# yard-ice-cpu.net
KiCad netlist of a schematic drawn in Altium Designer
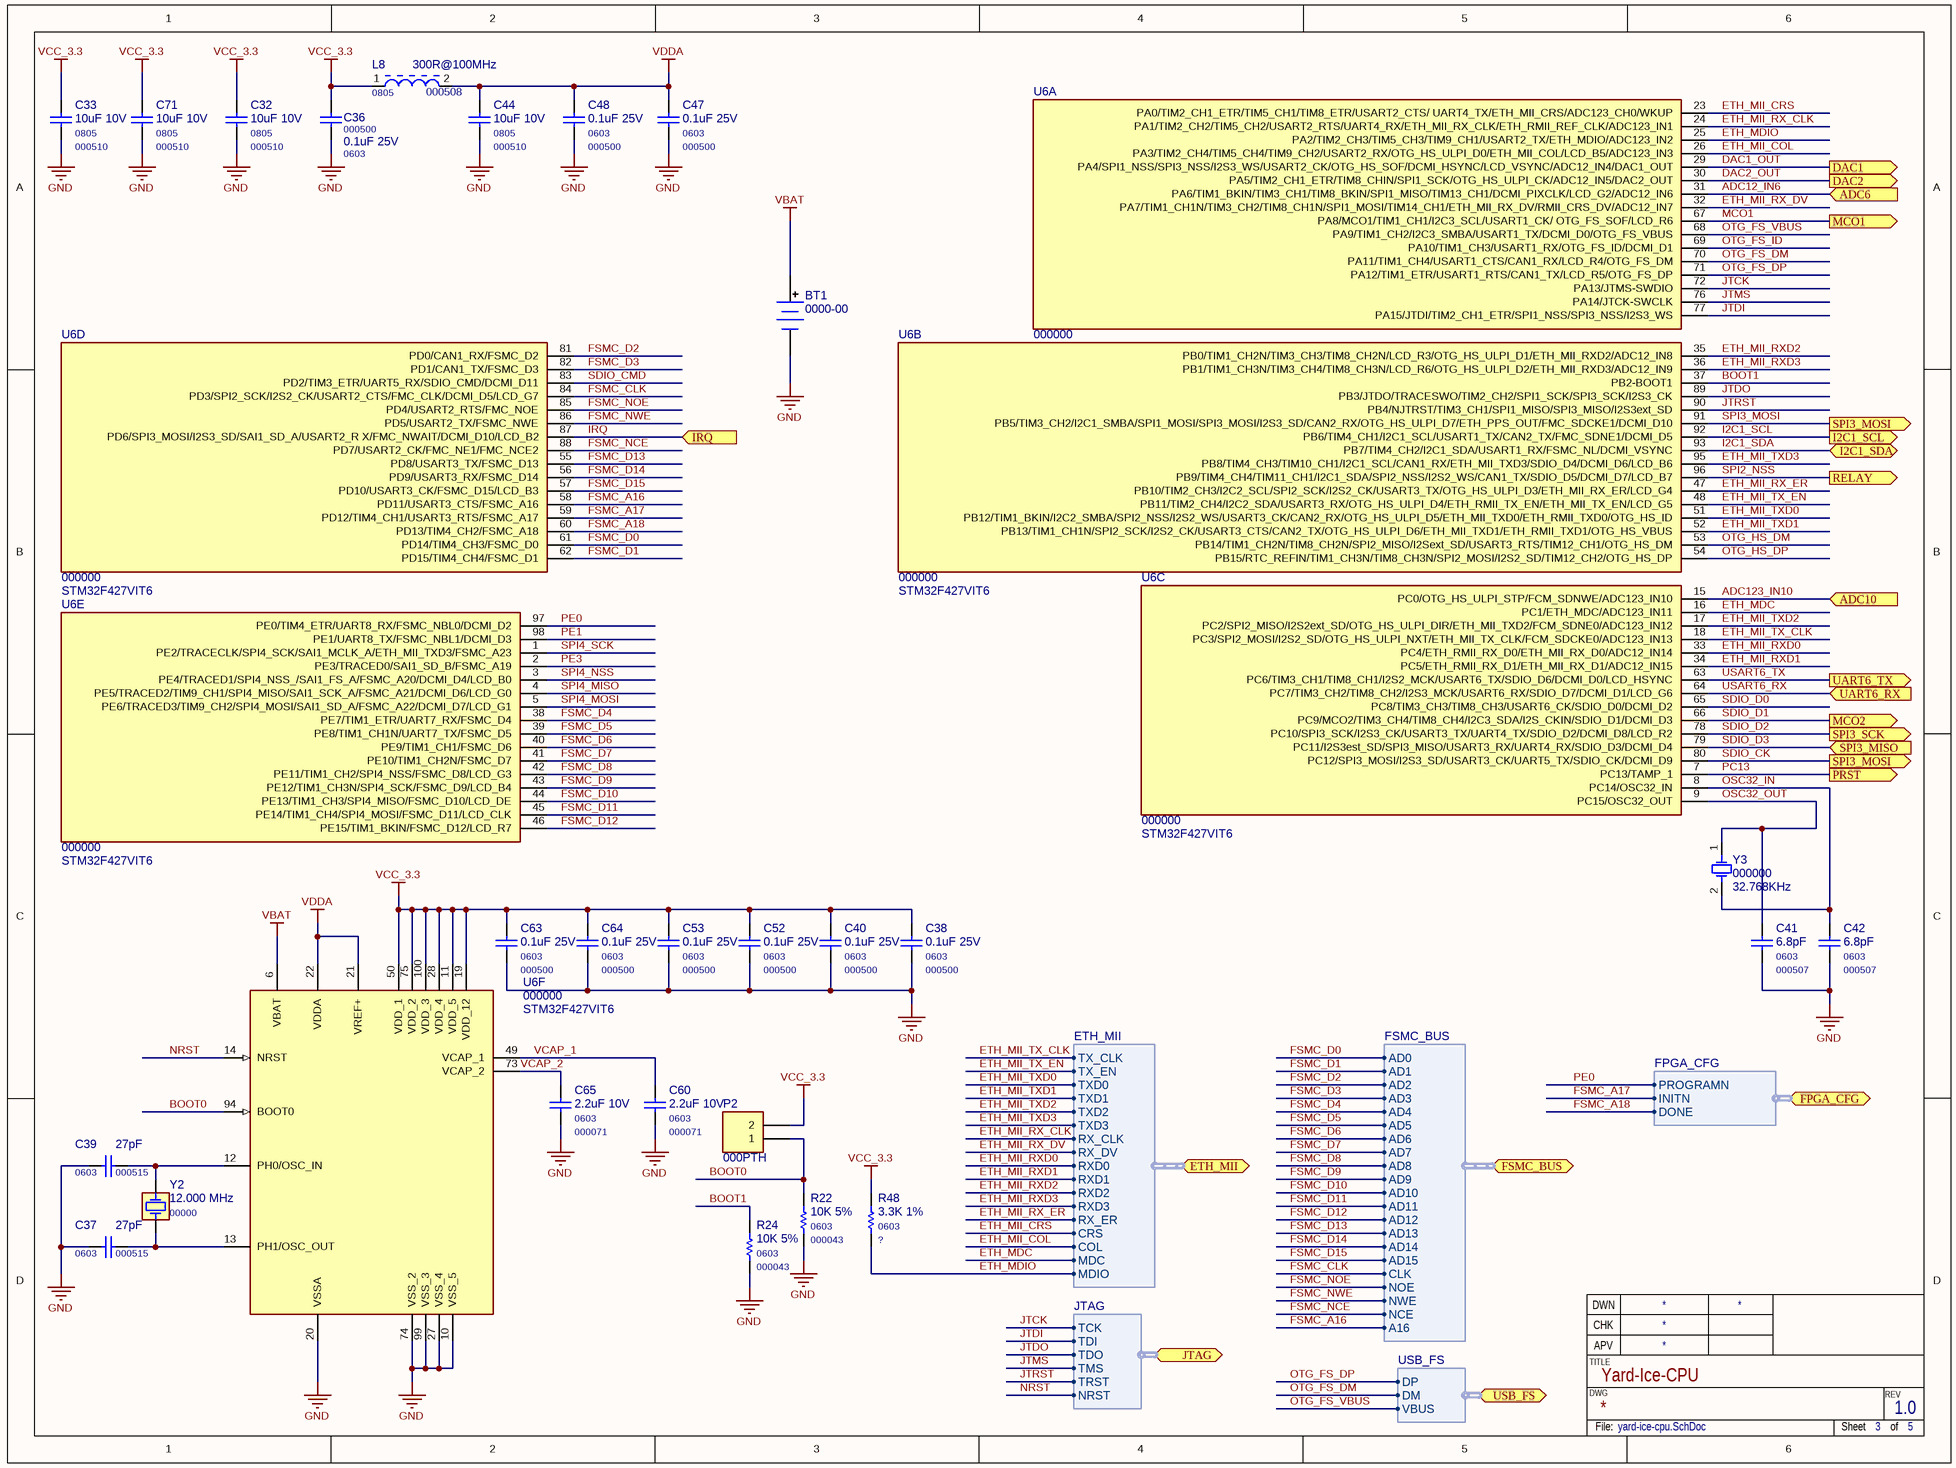
[diagram p0: yard-ice-cpu.SchDoc]

(export (version "E")
  (design (tool "Eeschema 10.0.6"))
  (components
    (comp (ref "BT1")
      (value "0000-00")
      (footprint "CR-1632/VCN")
      (description "PTH 16mm SMD Battery Vertical")
      (fields (field (name "MF") "Panasonic"))
      (libsource (lib "discrete-pth") (part "CR-1632/VCN"))
    )
    (comp (ref "C32")
      (value "TDK")
      (footprint "C0805M")
      (description "SMD Ceramic Chip Capacitor - 0805 - X7R")
      (fields (field (name "ALTIUM_VALUE") "10uF 10V") (field (name "PACKAGE") "0805"))
      (libsource (lib "discrete-sm") (part "C0805"))
    )
    (comp (ref "C33")
      (value "TDK")
      (footprint "C0805M")
      (description "SMD Ceramic Chip Capacitor - 0805 - X7R")
      (fields (field (name "ALTIUM_VALUE") "10uF 10V") (field (name "PACKAGE") "0805"))
      (libsource (lib "discrete-sm") (part "C0805"))
    )
    (comp (ref "C36")
      (value "000500")
      (footprint "C0603M")
      (description "SMD Ceramic Chip Capacitor - 0603 - X7R")
      (fields
        (field (name "ALTIUM_VALUE") "0.1uF 25V")
        (field (name "PACKAGE") "0603")
        (field (name "MF") "TDK")
      )
      (libsource (lib "discrete-sm") (part "C0603"))
    )
    (comp (ref "C37")
      (value "000515")
      (footprint "C0603M")
      (description "SMD Ceramic Chip Capacitor - 0603")
      (fields (field (name "ALTIUM_VALUE") "27pF") (field (name "PACKAGE") "0603"))
      (libsource (lib "discrete-sm") (part "C0603"))
    )
    (comp (ref "C38")
      (value "000500")
      (footprint "C0603M")
      (description "SMD Ceramic Chip Capacitor - 0603 - X7R")
      (fields
        (field (name "ALTIUM_VALUE") "0.1uF 25V")
        (field (name "PACKAGE") "0603")
        (field (name "MF") "TDK")
      )
      (libsource (lib "discrete-sm") (part "C0603"))
    )
    (comp (ref "C39")
      (value "000515")
      (footprint "C0603M")
      (description "SMD Ceramic Chip Capacitor - 0603")
      (fields (field (name "ALTIUM_VALUE") "27pF") (field (name "PACKAGE") "0603"))
      (libsource (lib "discrete-sm") (part "C0603"))
    )
    (comp (ref "C40")
      (value "000500")
      (footprint "C0603M")
      (description "SMD Ceramic Chip Capacitor - 0603 - X7R")
      (fields
        (field (name "ALTIUM_VALUE") "0.1uF 25V")
        (field (name "PACKAGE") "0603")
        (field (name "MF") "TDK")
      )
      (libsource (lib "discrete-sm") (part "C0603"))
    )
    (comp (ref "C41")
      (value "000507")
      (footprint "C0603M")
      (description "SMD Ceramic Chip Capacitor - 0603")
      (fields (field (name "ALTIUM_VALUE") "6.8pF") (field (name "PACKAGE") "0603"))
      (libsource (lib "discrete-sm") (part "C0603"))
    )
    (comp (ref "C42")
      (value "000507")
      (footprint "C0603M")
      (description "SMD Ceramic Chip Capacitor - 0603")
      (fields (field (name "ALTIUM_VALUE") "6.8pF") (field (name "PACKAGE") "0603"))
      (libsource (lib "discrete-sm") (part "C0603"))
    )
    (comp (ref "C44")
      (value "000510")
      (footprint "C0805M")
      (description "SMD Ceramic Chip Capacitor - 0805 - X7R")
      (fields
        (field (name "ALTIUM_VALUE") "10uF 10V")
        (field (name "PACKAGE") "0805")
        (field (name "MF") "TDK")
      )
      (libsource (lib "discrete-sm") (part "C0805"))
    )
    (comp (ref "C47")
      (value "000500")
      (footprint "C0603M")
      (description "SMD Ceramic Chip Capacitor - 0603 - X7R")
      (fields
        (field (name "ALTIUM_VALUE") "0.1uF 25V")
        (field (name "PACKAGE") "0603")
        (field (name "MF") "TDK")
      )
      (libsource (lib "discrete-sm") (part "C0603"))
    )
    (comp (ref "C48")
      (value "000500")
      (footprint "C0603M")
      (description "SMD Ceramic Chip Capacitor - 0603 - X7R")
      (fields
        (field (name "ALTIUM_VALUE") "0.1uF 25V")
        (field (name "PACKAGE") "0603")
        (field (name "MF") "TDK")
      )
      (libsource (lib "discrete-sm") (part "C0603"))
    )
    (comp (ref "C52")
      (value "000500")
      (footprint "C0603M")
      (description "SMD Ceramic Chip Capacitor - 0603 - X7R")
      (fields
        (field (name "ALTIUM_VALUE") "0.1uF 25V")
        (field (name "PACKAGE") "0603")
        (field (name "MF") "TDK")
      )
      (libsource (lib "discrete-sm") (part "C0603"))
    )
    (comp (ref "C53")
      (value "000500")
      (footprint "C0603M")
      (description "SMD Ceramic Chip Capacitor - 0603 - X7R")
      (fields
        (field (name "ALTIUM_VALUE") "0.1uF 25V")
        (field (name "PACKAGE") "0603")
        (field (name "MF") "TDK")
      )
      (libsource (lib "discrete-sm") (part "C0603"))
    )
    (comp (ref "C60")
      (value "000071")
      (footprint "C0603M")
      (description "SMD Ceramic Chip Capacitor - 0603 - X7R")
      (fields
        (field (name "ALTIUM_VALUE") "2.2uF 10V")
        (field (name "PACKAGE") "0603")
        (field (name "MF") "Taiyo Yuden")
      )
      (libsource (lib "discrete-sm") (part "C0603"))
    )
    (comp (ref "C63")
      (value "000500")
      (footprint "C0603M")
      (description "SMD Ceramic Chip Capacitor - 0603 - X7R")
      (fields
        (field (name "ALTIUM_VALUE") "0.1uF 25V")
        (field (name "PACKAGE") "0603")
        (field (name "MF") "TDK")
      )
      (libsource (lib "discrete-sm") (part "C0603"))
    )
    (comp (ref "C64")
      (value "000500")
      (footprint "C0603M")
      (description "SMD Ceramic Chip Capacitor - 0603 - X7R")
      (fields
        (field (name "ALTIUM_VALUE") "0.1uF 25V")
        (field (name "PACKAGE") "0603")
        (field (name "MF") "TDK")
      )
      (libsource (lib "discrete-sm") (part "C0603"))
    )
    (comp (ref "C65")
      (value "000071")
      (footprint "C0603M")
      (description "SMD Ceramic Chip Capacitor - 0603 - X7R")
      (fields
        (field (name "ALTIUM_VALUE") "2.2uF 10V")
        (field (name "PACKAGE") "0603")
        (field (name "MF") "Taiyo Yuden")
      )
      (libsource (lib "discrete-sm") (part "C0603"))
    )
    (comp (ref "C71")
      (value "TDK")
      (footprint "C0805M")
      (description "SMD Ceramic Chip Capacitor - 0805 - X7R")
      (fields (field (name "ALTIUM_VALUE") "10uF 10V") (field (name "PACKAGE") "0805"))
      (libsource (lib "discrete-sm") (part "C0805"))
    )
    (comp (ref "L8")
      (value "000508")
      (footprint "L0805M")
      (description "SMD Ferrite Bead 0805")
      (fields
        (field (name "ALTIUM_VALUE") "300R@100MHz")
        (field (name "PACKAGE") "0805")
        (field (name "MF") "TDK")
      )
      (libsource (lib "discrete-sm") (part "L0805"))
    )
    (comp (ref "P2")
      (value "000PTH")
      (footprint "TSW-102-07-G-S")
      (description "Header, 2-Pin")
      (libsource (lib "samtec-board-to-board") (part "Header 2"))
    )
    (comp (ref "R22")
      (value "000043")
      (footprint "R0603M")
      (description "SMD Chip Resistor - 0603")
      (fields (field (name "ALTIUM_VALUE") "10K 5%") (field (name "PACKAGE") "0603"))
      (libsource (lib "discrete-sm") (part "R0603"))
    )
    (comp (ref "R24")
      (value "000043")
      (footprint "R0603M")
      (description "SMD Chip Resistor - 0603")
      (fields (field (name "ALTIUM_VALUE") "10K 5%") (field (name "PACKAGE") "0603"))
      (libsource (lib "discrete-sm") (part "R0603"))
    )
    (comp (ref "R48")
      (value "?")
      (footprint "R0603M")
      (description "SMD Chip Resistor - 0603")
      (fields (field (name "ALTIUM_VALUE") "3.3K 1%") (field (name "PACKAGE") "0603"))
      (libsource (lib "discrete-sm") (part "R0603"))
    )
    (comp (ref "U6")
      (value "000000")
      (footprint "LQFP100")
      (description "ARM Cortex-M4,  2MB Flash, 256+4KB RAM")
      (fields (field (name "ALTIUM_VALUE") "STM32F427VIT6"))
      (libsource (lib "st") (part "STM32F427VIT6"))
    )
    (comp (ref "Y2")
      (value "00000")
      (footprint "ABM3-H")
      (description "Miniature Ceramic SMD Crystal")
      (fields (field (name "MF") "Abracon") (field (name "ALTIUM_VALUE") "12.000 MHz"))
      (libsource (lib "abracon") (part "ABM3"))
    )
    (comp (ref "Y3")
      (value "000000")
      (footprint "CA-301-V")
      (description "Cylinder Crystal Unit")
      (fields (field (name "MF") "Epson") (field (name "ALTIUM_VALUE") "32.768KHz"))
      (libsource (lib "epson-xtal") (part "CA-301"))
    )
  )
  (nets
    (net (code "6") (name "/ADC12_IN6") (class "Default")
      (node (ref "U6") (pin "31") (pinfunction "PA6/TIM1_BKIN/TIM3_CH1/TIM8_BKIN/SPI1_MISO/TIM13_CH1/DCMI_PIXCLK/LCD_G2/ADC12_IN6_31") (pintype "tri_state"))
    )
    (net (code "7") (name "/ADC123_IN10") (class "Default")
      (node (ref "U6") (pin "15") (pinfunction "PC0/OTG_HS_ULPI_STP/FCM_SDNWE/ADC123_IN10_15") (pintype "tri_state"))
    )
    (net (code "8") (name "/BOOT0") (class "Default")
      (node (ref "P2") (pin "1") (pinfunction "1_1") (pintype "passive"))
      (node (ref "R22") (pin "2") (pinfunction "2_2") (pintype "passive"))
      (node (ref "U6") (pin "94") (pinfunction "BOOT0_94") (pintype "input"))
    )
    (net (code "9") (name "/BOOT1") (class "Default")
      (node (ref "R24") (pin "2") (pinfunction "2_2") (pintype "passive"))
      (node (ref "U6") (pin "37") (pinfunction "PB2-BOOT1_37") (pintype "tri_state"))
    )
    (net (code "10") (name "/DAC1_OUT") (class "Default")
      (node (ref "U6") (pin "29") (pinfunction "PA4/SPI1_NSS/SPI3_NSS/I2S3_WS/USART2_CK/OTG_HS_SOF/DCMI_HSYNC/LCD_VSYNC/ADC12_IN4/DAC1_OUT_29") (pintype "tri_state"))
    )
    (net (code "11") (name "/DAC2_OUT") (class "Default")
      (node (ref "U6") (pin "30") (pinfunction "PA5/TIM2_CH1_ETR/TIM8_CHIN/SPI1_SCK/OTG_HS_ULPI_CK/ADC12_IN5/DAC2_OUT_30") (pintype "tri_state"))
    )
    (net (code "12") (name "/ETH_MDC") (class "Default")
      (node (ref "U6") (pin "16") (pinfunction "PC1/ETH_MDC/ADC123_IN11_16") (pintype "tri_state"))
    )
    (net (code "13") (name "/ETH_MDIO") (class "Default")
      (node (ref "R48") (pin "1") (pinfunction "1_1") (pintype "passive"))
      (node (ref "U6") (pin "25") (pinfunction "PA2/TIM2_CH3/TIM5_CH3/TIM9_CH1/USART2_TX/ETH_MDIO/ADC123_IN2_25") (pintype "tri_state"))
    )
    (net (code "14") (name "/ETH_MII_COL") (class "Default")
      (node (ref "U6") (pin "26") (pinfunction "PA3/TIM2_CH4/TIM5_CH4/TIM9_CH2/USART2_RX/OTG_HS_ULPI_D0/ETH_MII_COL/LCD_B5/ADC123_IN3_26") (pintype "tri_state"))
    )
    (net (code "15") (name "/ETH_MII_CRS") (class "Default")
      (node (ref "U6") (pin "23") (pinfunction "PA0/TIM2_CH1_ETR/TIM5_CH1/TIM8_ETR/USART2_CTS/_UART4_TX/ETH_MII_CRS/ADC123_CH0/WKUP_23") (pintype "tri_state"))
    )
    (net (code "16") (name "/ETH_MII_RXD0") (class "Default")
      (node (ref "U6") (pin "33") (pinfunction "PC4/ETH_RMII_RX_D0/ETH_MII_RX_D0/ADC12_IN14_33") (pintype "tri_state"))
    )
    (net (code "17") (name "/ETH_MII_RXD1") (class "Default")
      (node (ref "U6") (pin "34") (pinfunction "PC5/ETH_RMII_RX_D1/ETH_MII_RX_D1/ADC12_IN15_34") (pintype "tri_state"))
    )
    (net (code "18") (name "/ETH_MII_RXD2") (class "Default")
      (node (ref "U6") (pin "35") (pinfunction "PB0/TIM1_CH2N/TIM3_CH3/TIM8_CH2N/LCD_R3/OTG_HS_ULPI_D1/ETH_MII_RXD2/ADC12_IN8_35") (pintype "tri_state"))
    )
    (net (code "19") (name "/ETH_MII_RXD3") (class "Default")
      (node (ref "U6") (pin "36") (pinfunction "PB1/TIM1_CH3N/TIM3_CH4/TIM8_CH3N/LCD_R6/OTG_HS_ULPI_D2/ETH_MII_RXD3/ADC12_IN9_36") (pintype "tri_state"))
    )
    (net (code "20") (name "/ETH_MII_RX_CLK") (class "Default")
      (node (ref "U6") (pin "24") (pinfunction "PA1/TIM2_CH2/TIM5_CH2/USART2_RTS/UART4_RX/ETH_MII_RX_CLK/ETH_RMII_REF_CLK/ADC123_IN1_24") (pintype "tri_state"))
    )
    (net (code "21") (name "/ETH_MII_RX_DV") (class "Default")
      (node (ref "U6") (pin "32") (pinfunction "PA7/TIM1_CH1N/TIM3_CH2/TIM8_CH1N/SPI1_MOSI/TIM14_CH1/ETH_MII_RX_DV/RMII_CRS_DV/ADC12_IN7_32") (pintype "tri_state"))
    )
    (net (code "22") (name "/ETH_MII_RX_ER") (class "Default")
      (node (ref "U6") (pin "47") (pinfunction "PB10/TIM2_CH3/I2C2_SCL/SPI2_SCK/I2S2_CK/USART3_TX/OTG_HS_ULPI_D3/ETH_MII_RX_ER/LCD_G4_47") (pintype "tri_state"))
    )
    (net (code "23") (name "/ETH_MII_TXD0") (class "Default")
      (node (ref "U6") (pin "51") (pinfunction "PB12/TIM1_BKIN/I2C2_SMBA/SPI2_NSS/I2S2_WS/USART3_CK/CAN2_RX/OTG_HS_ULPI_D5/ETH_MII_TXD0/ETH_RMII_TXD0/OTG_HS_ID_51") (pintype "tri_state"))
    )
    (net (code "24") (name "/ETH_MII_TXD1") (class "Default")
      (node (ref "U6") (pin "52") (pinfunction "PB13/TIM1_CH1N/SPI2_SCK/I2S2_CK/USART3_CTS/CAN2_TX/OTG_HS_ULPI_D6/ETH_MII_TXD1/ETH_RMII_TXD1/OTG_HS_VBUS_52") (pintype "tri_state"))
    )
    (net (code "25") (name "/ETH_MII_TXD2") (class "Default")
      (node (ref "U6") (pin "17") (pinfunction "PC2/SPI2_MISO/I2S2ext_SD/OTG_HS_ULPI_DIR/ETH_MII_TXD2/FCM_SDNE0/ADC123_IN12_17") (pintype "tri_state"))
    )
    (net (code "26") (name "/ETH_MII_TXD3") (class "Default")
      (node (ref "U6") (pin "95") (pinfunction "PB8/TIM4_CH3/TIM10_CH1/I2C1_SCL/CAN1_RX/ETH_MII_TXD3/SDIO_D4/DCMI_D6/LCD_B6_95") (pintype "tri_state"))
    )
    (net (code "27") (name "/ETH_MII_TX_CLK") (class "Default")
      (node (ref "U6") (pin "18") (pinfunction "PC3/SPI2_MOSI/I2S2_SD/OTG_HS_ULPI_NXT/ETH_MII_TX_CLK/FCM_SDCKE0/ADC123_IN13_18") (pintype "tri_state"))
    )
    (net (code "28") (name "/ETH_MII_TX_EN") (class "Default")
      (node (ref "U6") (pin "48") (pinfunction "PB11/TIM2_CH4/I2C2_SDA/USART3_RX/OTG_HS_ULPI_D4/ETH_RMII_TX_EN/ETH_MII_TX_EN/LCD_G5_48") (pintype "tri_state"))
    )
    (net (code "29") (name "/FSMC_A16") (class "Default")
      (node (ref "U6") (pin "58") (pinfunction "PD11/USART3_CTS/FSMC_A16_58") (pintype "tri_state"))
    )
    (net (code "30") (name "/FSMC_A17") (class "Default")
      (node (ref "U6") (pin "59") (pinfunction "PD12/TIM4_CH1/USART3_RTS/FSMC_A17_59") (pintype "tri_state"))
    )
    (net (code "31") (name "/FSMC_A18") (class "Default")
      (node (ref "U6") (pin "60") (pinfunction "PD13/TIM4_CH2/FSMC_A18_60") (pintype "tri_state"))
    )
    (net (code "32") (name "/FSMC_CLK") (class "Default")
      (node (ref "U6") (pin "84") (pinfunction "PD3/SPI2_SCK/I2S2_CK/USART2_CTS/FMC_CLK/DCMI_D5/LCD_G7_84") (pintype "tri_state"))
    )
    (net (code "33") (name "/FSMC_D0") (class "Default")
      (node (ref "U6") (pin "61") (pinfunction "PD14/TIM4_CH3/FSMC_D0_61") (pintype "tri_state"))
    )
    (net (code "34") (name "/FSMC_D1") (class "Default")
      (node (ref "U6") (pin "62") (pinfunction "PD15/TIM4_CH4/FSMC_D1_62") (pintype "tri_state"))
    )
    (net (code "35") (name "/FSMC_D2") (class "Default")
      (node (ref "U6") (pin "81") (pinfunction "PD0/CAN1_RX/FSMC_D2_81") (pintype "tri_state"))
    )
    (net (code "36") (name "/FSMC_D3") (class "Default")
      (node (ref "U6") (pin "82") (pinfunction "PD1/CAN1_TX/FSMC_D3_82") (pintype "tri_state"))
    )
    (net (code "37") (name "/FSMC_D4") (class "Default")
      (node (ref "U6") (pin "38") (pinfunction "PE7/TIM1_ETR/UART7_RX/FSMC_D4_38") (pintype "tri_state"))
    )
    (net (code "38") (name "/FSMC_D5") (class "Default")
      (node (ref "U6") (pin "39") (pinfunction "PE8/TIM1_CH1N/UART7_TX/FSMC_D5_39") (pintype "tri_state"))
    )
    (net (code "39") (name "/FSMC_D6") (class "Default")
      (node (ref "U6") (pin "40") (pinfunction "PE9/TIM1_CH1/FSMC_D6_40") (pintype "tri_state"))
    )
    (net (code "40") (name "/FSMC_D7") (class "Default")
      (node (ref "U6") (pin "41") (pinfunction "PE10/TIM1_CH2N/FSMC_D7_41") (pintype "tri_state"))
    )
    (net (code "41") (name "/FSMC_D8") (class "Default")
      (node (ref "U6") (pin "42") (pinfunction "PE11/TIM1_CH2/SPI4_NSS/FSMC_D8/LCD_G3_42") (pintype "tri_state"))
    )
    (net (code "42") (name "/FSMC_D9") (class "Default")
      (node (ref "U6") (pin "43") (pinfunction "PE12/TIM1_CH3N/SPI4_SCK/FSMC_D9/LCD_B4_43") (pintype "tri_state"))
    )
    (net (code "43") (name "/FSMC_D10") (class "Default")
      (node (ref "U6") (pin "44") (pinfunction "PE13/TIM1_CH3/SPI4_MISO/FSMC_D10/LCD_DE_44") (pintype "tri_state"))
    )
    (net (code "44") (name "/FSMC_D11") (class "Default")
      (node (ref "U6") (pin "45") (pinfunction "PE14/TIM1_CH4/SPI4_MOSI/FSMC_D11/LCD_CLK_45") (pintype "tri_state"))
    )
    (net (code "45") (name "/FSMC_D12") (class "Default")
      (node (ref "U6") (pin "46") (pinfunction "PE15/TIM1_BKIN/FSMC_D12/LCD_R7_46") (pintype "tri_state"))
    )
    (net (code "46") (name "/FSMC_D13") (class "Default")
      (node (ref "U6") (pin "55") (pinfunction "PD8/USART3_TX/FSMC_D13_55") (pintype "tri_state"))
    )
    (net (code "47") (name "/FSMC_D14") (class "Default")
      (node (ref "U6") (pin "56") (pinfunction "PD9/USART3_RX/FSMC_D14_56") (pintype "tri_state"))
    )
    (net (code "48") (name "/FSMC_D15") (class "Default")
      (node (ref "U6") (pin "57") (pinfunction "PD10/USART3_CK/FSMC_D15/LCD_B3_57") (pintype "tri_state"))
    )
    (net (code "49") (name "/FSMC_NCE") (class "Default")
      (node (ref "U6") (pin "88") (pinfunction "PD7/USART2_CK/FMC_NE1/FMC_NCE2_88") (pintype "tri_state"))
    )
    (net (code "50") (name "/FSMC_NOE") (class "Default")
      (node (ref "U6") (pin "85") (pinfunction "PD4/USART2_RTS/FMC_NOE_85") (pintype "tri_state"))
    )
    (net (code "51") (name "/FSMC_NWE") (class "Default")
      (node (ref "U6") (pin "86") (pinfunction "PD5/USART2_TX/FSMC_NWE_86") (pintype "tri_state"))
    )
    (net (code "52") (name "/I2C1_SCL") (class "Default")
      (node (ref "U6") (pin "92") (pinfunction "PB6/TIM4_CH1/I2C1_SCL/USART1_TX/CAN2_TX/FMC_SDNE1/DCMI_D5_92") (pintype "tri_state"))
    )
    (net (code "53") (name "/I2C1_SDA") (class "Default")
      (node (ref "U6") (pin "93") (pinfunction "PB7/TIM4_CH2/I2C1_SDA/USART1_RX/FSMC_NL/DCMI_VSYNC_93") (pintype "tri_state"))
    )
    (net (code "54") (name "/IRQ") (class "Default")
      (node (ref "U6") (pin "87") (pinfunction "PD6/SPI3_MOSI/I2S3_SD/SAI1_SD_A/USART2_R_X/FMC_NWAIT/DCMI_D10/LCD_B2_87") (pintype "tri_state"))
    )
    (net (code "55") (name "/JTCK") (class "Default")
      (node (ref "U6") (pin "72") (pinfunction "PA13/JTMS-SWDIO_72") (pintype "tri_state"))
    )
    (net (code "56") (name "/JTDI") (class "Default")
      (node (ref "U6") (pin "77") (pinfunction "PA15/JTDI/TIM2_CH1_ETR/SPI1_NSS/SPI3_NSS/I2S3_WS_77") (pintype "tri_state"))
    )
    (net (code "57") (name "/JTDO") (class "Default")
      (node (ref "U6") (pin "89") (pinfunction "PB3/JTDO/TRACESWO/TIM2_CH2/SPI1_SCK/SPI3_SCK/I2S3_CK_89") (pintype "tri_state"))
    )
    (net (code "58") (name "/JTMS") (class "Default")
      (node (ref "U6") (pin "76") (pinfunction "PA14/JTCK-SWCLK_76") (pintype "tri_state"))
    )
    (net (code "59") (name "/JTRST") (class "Default")
      (node (ref "U6") (pin "90") (pinfunction "PB4/NJTRST/TIM3_CH1/SPI1_MISO/SPI3_MISO/I2S3ext_SD_90") (pintype "tri_state"))
    )
    (net (code "60") (name "/MCO1") (class "Default")
      (node (ref "U6") (pin "67") (pinfunction "PA8/MCO1/TIM1_CH1/I2C3_SCL/USART1_CK/_OTG_FS_SOF/LCD_R6_67") (pintype "tri_state"))
    )
    (net (code "61") (name "/NRST") (class "Default")
      (node (ref "U6") (pin "14") (pinfunction "NRST_14") (pintype "input"))
    )
    (net (code "62") (name "/OSC32_IN") (class "Default")
      (node (ref "C42") (pin "2") (pinfunction "2_2") (pintype "passive"))
      (node (ref "U6") (pin "8") (pinfunction "PC14/OSC32_IN_8") (pintype "tri_state"))
      (node (ref "Y3") (pin "2") (pinfunction "2_2") (pintype "passive"))
    )
    (net (code "63") (name "/OSC32_OUT") (class "Default")
      (node (ref "C41") (pin "2") (pinfunction "2_2") (pintype "passive"))
      (node (ref "U6") (pin "9") (pinfunction "PC15/OSC32_OUT_9") (pintype "tri_state"))
      (node (ref "Y3") (pin "1") (pinfunction "1_1") (pintype "passive"))
    )
    (net (code "64") (name "/OTG_FS_DM") (class "Default")
      (node (ref "U6") (pin "70") (pinfunction "PA11/TIM1_CH4/USART1_CTS/CAN1_RX/LCD_R4/OTG_FS_DM_70") (pintype "tri_state"))
    )
    (net (code "65") (name "/OTG_FS_DP") (class "Default")
      (node (ref "U6") (pin "71") (pinfunction "PA12/TIM1_ETR/USART1_RTS/CAN1_TX/LCD_R5/OTG_FS_DP_71") (pintype "tri_state"))
    )
    (net (code "66") (name "/OTG_FS_ID") (class "Default")
      (node (ref "U6") (pin "69") (pinfunction "PA10/TIM1_CH3/USART1_RX/OTG_FS_ID/DCMI_D1_69") (pintype "tri_state"))
    )
    (net (code "67") (name "/OTG_FS_VBUS") (class "Default")
      (node (ref "U6") (pin "68") (pinfunction "PA9/TIM1_CH2/I2C3_SMBA/USART1_TX/DCMI_D0/OTG_FS_VBUS_68") (pintype "tri_state"))
    )
    (net (code "68") (name "/OTG_HS_DM") (class "Default")
      (node (ref "U6") (pin "53") (pinfunction "PB14/TIM1_CH2N/TIM8_CH2N/SPI2_MISO/I2Sext_SD/USART3_RTS/TIM12_CH1/OTG_HS_DM_53") (pintype "tri_state"))
    )
    (net (code "69") (name "/OTG_HS_DP") (class "Default")
      (node (ref "U6") (pin "54") (pinfunction "PB15/RTC_REFIN/TIM1_CH3N/TIM8_CH3N/SPI2_MOSI/I2S2_SD/TIM12_CH2/OTG_HS_DP_54") (pintype "tri_state"))
    )
    (net (code "70") (name "/PC13") (class "Default")
      (node (ref "U6") (pin "7") (pinfunction "PC13/TAMP_1_7") (pintype "tri_state"))
    )
    (net (code "71") (name "/PE0") (class "Default")
      (node (ref "U6") (pin "97") (pinfunction "PE0/TIM4_ETR/UART8_RX/FSMC_NBL0/DCMI_D2_97") (pintype "tri_state"))
    )
    (net (code "72") (name "/PE1") (class "Default")
      (node (ref "U6") (pin "98") (pinfunction "PE1/UART8_TX/FSMC_NBL1/DCMI_D3_98") (pintype "tri_state"))
    )
    (net (code "73") (name "/PE3") (class "Default")
      (node (ref "U6") (pin "2") (pinfunction "PE3/TRACED0/SAI1_SD_B/FSMC_A19_2") (pintype "tri_state"))
    )
    (net (code "74") (name "/SDIO_CK") (class "Default")
      (node (ref "U6") (pin "80") (pinfunction "PC12/SPI3_MOSI/I2S3_SD/USART3_CK/UART5_TX/SDIO_CK/DCMI_D9_80") (pintype "tri_state"))
      (node (ref "U6") (pin "91") (pinfunction "PB5/TIM3_CH2/I2C1_SMBA/SPI1_MOSI/SPI3_MOSI/I2S3_SD/CAN2_RX/OTG_HS_ULPI_D7/ETH_PPS_OUT/FMC_SDCKE1/DCMI_D10_91") (pintype "tri_state"))
    )
    (net (code "75") (name "/SDIO_CMD") (class "Default")
      (node (ref "U6") (pin "83") (pinfunction "PD2/TIM3_ETR/UART5_RX/SDIO_CMD/DCMI_D11_83") (pintype "tri_state"))
    )
    (net (code "76") (name "/SDIO_D0") (class "Default")
      (node (ref "U6") (pin "65") (pinfunction "PC8/TIM3_CH3/TIM8_CH3/USART6_CK/SDIO_D0/DCMI_D2_65") (pintype "tri_state"))
    )
    (net (code "77") (name "/SDIO_D1") (class "Default")
      (node (ref "U6") (pin "66") (pinfunction "PC9/MCO2/TIM3_CH4/TIM8_CH4/I2C3_SDA/I2S_CKIN/SDIO_D1/DCMI_D3_66") (pintype "tri_state"))
    )
    (net (code "78") (name "/SDIO_D2") (class "Default")
      (node (ref "U6") (pin "78") (pinfunction "PC10/SPI3_SCK/I2S3_CK/USART3_TX/UART4_TX/SDIO_D2/DCMI_D8/LCD_R2_78") (pintype "tri_state"))
    )
    (net (code "79") (name "/SDIO_D3") (class "Default")
      (node (ref "U6") (pin "79") (pinfunction "PC11/I2S3est_SD/SPI3_MISO/USART3_RX/UART4_RX/SDIO_D3/DCMI_D4_79") (pintype "tri_state"))
    )
    (net (code "80") (name "/SPI2_NSS") (class "Default")
      (node (ref "U6") (pin "96") (pinfunction "PB9/TIM4_CH4/TIM11_CH1/I2C1_SDA/SPI2_NSS/I2S2_WS/CAN1_TX/SDIO_D5/DCMI_D7/LCD_B7_96") (pintype "tri_state"))
    )
    (net (code "81") (name "/SPI4_MISO") (class "Default")
      (node (ref "U6") (pin "4") (pinfunction "PE5/TRACED2/TIM9_CH1/SPI4_MISO/SAI1_SCK_A/FSMC_A21/DCMI_D6/LCD_G0_4") (pintype "tri_state"))
    )
    (net (code "82") (name "/SPI4_MOSI") (class "Default")
      (node (ref "U6") (pin "5") (pinfunction "PE6/TRACED3/TIM9_CH2/SPI4_MOSI/SAI1_SD_A/FSMC_A22/DCMI_D7/LCD_G1_5") (pintype "tri_state"))
    )
    (net (code "83") (name "/SPI4_NSS") (class "Default")
      (node (ref "U6") (pin "3") (pinfunction "PE4/TRACED1/SPI4_NSS_/SAI1_FS_A/FSMC_A20/DCMI_D4/LCD_B0_3") (pintype "tri_state"))
    )
    (net (code "84") (name "/SPI4_SCK") (class "Default")
      (node (ref "U6") (pin "1") (pinfunction "PE2/TRACECLK/SPI4_SCK/SAI1_MCLK_A/ETH_MII_TXD3/FSMC_A23_1") (pintype "tri_state"))
    )
    (net (code "85") (name "/USART6_RX") (class "Default")
      (node (ref "U6") (pin "64") (pinfunction "PC7/TIM3_CH2/TIM8_CH2/I2S3_MCK/USART6_RX/SDIO_D7/DCMI_D1/LCD_G6_64") (pintype "tri_state"))
    )
    (net (code "86") (name "/USART6_TX") (class "Default")
      (node (ref "U6") (pin "63") (pinfunction "PC6/TIM3_CH1/TIM8_CH1/I2S2_MCK/USART6_TX/SDIO_D6/DCMI_D0/LCD_HSYNC_63") (pintype "tri_state"))
    )
    (net (code "87") (name "/VCAP_1") (class "Default")
      (node (ref "C60") (pin "1") (pinfunction "1_1") (pintype "passive"))
      (node (ref "U6") (pin "49") (pinfunction "VCAP_1_49") (pintype "power_in"))
    )
    (net (code "88") (name "/VCAP_2") (class "Default")
      (node (ref "C65") (pin "1") (pinfunction "1_1") (pintype "passive"))
      (node (ref "U6") (pin "73") (pinfunction "VCAP_2_73") (pintype "power_in"))
    )
    (net (code "94") (name "GND") (class "Default")
      (node (ref "BT1") (pin "2") (pinfunction "-_2") (pintype "passive"))
      (node (ref "C32") (pin "2") (pinfunction "2_2") (pintype "passive"))
      (node (ref "C33") (pin "2") (pinfunction "2_2") (pintype "passive"))
      (node (ref "C36") (pin "2") (pinfunction "2_2") (pintype "passive"))
      (node (ref "C37") (pin "1") (pinfunction "1_1") (pintype "passive"))
      (node (ref "C38") (pin "2") (pinfunction "2_2") (pintype "passive"))
      (node (ref "C39") (pin "1") (pinfunction "1_1") (pintype "passive"))
      (node (ref "C40") (pin "2") (pinfunction "2_2") (pintype "passive"))
      (node (ref "C41") (pin "1") (pinfunction "1_1") (pintype "passive"))
      (node (ref "C42") (pin "1") (pinfunction "1_1") (pintype "passive"))
      (node (ref "C44") (pin "2") (pinfunction "2_2") (pintype "passive"))
      (node (ref "C47") (pin "2") (pinfunction "2_2") (pintype "passive"))
      (node (ref "C48") (pin "2") (pinfunction "2_2") (pintype "passive"))
      (node (ref "C52") (pin "2") (pinfunction "2_2") (pintype "passive"))
      (node (ref "C53") (pin "2") (pinfunction "2_2") (pintype "passive"))
      (node (ref "C60") (pin "2") (pinfunction "2_2") (pintype "passive"))
      (node (ref "C63") (pin "2") (pinfunction "2_2") (pintype "passive"))
      (node (ref "C64") (pin "2") (pinfunction "2_2") (pintype "passive"))
      (node (ref "C65") (pin "2") (pinfunction "2_2") (pintype "passive"))
      (node (ref "C71") (pin "2") (pinfunction "2_2") (pintype "passive"))
      (node (ref "R22") (pin "1") (pinfunction "1_1") (pintype "passive"))
      (node (ref "R24") (pin "1") (pinfunction "1_1") (pintype "passive"))
      (node (ref "U6") (pin "10") (pinfunction "VSS_5_10") (pintype "power_in"))
      (node (ref "U6") (pin "20") (pinfunction "VSSA_20") (pintype "power_in"))
      (node (ref "U6") (pin "27") (pinfunction "VSS_4_27") (pintype "power_in"))
      (node (ref "U6") (pin "74") (pinfunction "VSS_2_74") (pintype "power_in"))
      (node (ref "U6") (pin "99") (pinfunction "VSS_3_99") (pintype "passive"))
    )
    (net (code "95") (name "Net-(U6F-PH0{slash}OSC_IN)") (class "Default")
      (node (ref "C39") (pin "2") (pinfunction "2_2") (pintype "passive"))
      (node (ref "U6") (pin "12") (pinfunction "PH0/OSC_IN_12") (pintype "tri_state"))
      (node (ref "Y2") (pin "1") (pinfunction "1_1") (pintype "passive"))
    )
    (net (code "96") (name "Net-(U6F-PH1{slash}OSC_OUT)") (class "Default")
      (node (ref "C37") (pin "2") (pinfunction "2_2") (pintype "passive"))
      (node (ref "U6") (pin "13") (pinfunction "PH1/OSC_OUT_13") (pintype "tri_state"))
      (node (ref "Y2") (pin "2") (pinfunction "2_2") (pintype "passive"))
    )
    (net (code "97") (name "VBAT") (class "Default")
      (node (ref "BT1") (pin "1") (pinfunction "+_1") (pintype "passive"))
      (node (ref "U6") (pin "6") (pinfunction "VBAT_6") (pintype "power_in"))
    )
    (net (code "98") (name "VCC_3.3") (class "Default")
      (node (ref "C32") (pin "1") (pinfunction "1_1") (pintype "passive"))
      (node (ref "C33") (pin "1") (pinfunction "1_1") (pintype "passive"))
      (node (ref "C36") (pin "1") (pinfunction "1_1") (pintype "passive"))
      (node (ref "C38") (pin "1") (pinfunction "1_1") (pintype "passive"))
      (node (ref "C40") (pin "1") (pinfunction "1_1") (pintype "passive"))
      (node (ref "C52") (pin "1") (pinfunction "1_1") (pintype "passive"))
      (node (ref "C53") (pin "1") (pinfunction "1_1") (pintype "passive"))
      (node (ref "C63") (pin "1") (pinfunction "1_1") (pintype "passive"))
      (node (ref "C64") (pin "1") (pinfunction "1_1") (pintype "passive"))
      (node (ref "C71") (pin "1") (pinfunction "1_1") (pintype "passive"))
      (node (ref "L8") (pin "1") (pinfunction "1_1") (pintype "passive"))
      (node (ref "P2") (pin "2") (pinfunction "2_2") (pintype "passive"))
      (node (ref "R48") (pin "2") (pinfunction "2_2") (pintype "passive"))
      (node (ref "U6") (pin "100") (pinfunction "VDD_3_100") (pintype "power_in"))
      (node (ref "U6") (pin "11") (pinfunction "VDD_5_11") (pintype "power_in"))
      (node (ref "U6") (pin "19") (pinfunction "VDD_12_19") (pintype "power_in"))
      (node (ref "U6") (pin "28") (pinfunction "VDD_4_28") (pintype "power_in"))
      (node (ref "U6") (pin "50") (pinfunction "VDD_1_50") (pintype "power_in"))
      (node (ref "U6") (pin "75") (pinfunction "VDD_2_75") (pintype "power_in"))
    )
    (net (code "99") (name "VDDA") (class "Default")
      (node (ref "C44") (pin "1") (pinfunction "1_1") (pintype "passive"))
      (node (ref "C47") (pin "1") (pinfunction "1_1") (pintype "passive"))
      (node (ref "C48") (pin "1") (pinfunction "1_1") (pintype "passive"))
      (node (ref "L8") (pin "2") (pinfunction "2_2") (pintype "passive"))
      (node (ref "U6") (pin "21") (pinfunction "VREF+_21") (pintype "power_in"))
      (node (ref "U6") (pin "22") (pinfunction "VDDA_22") (pintype "power_in"))
    )
  )
)
